# MCU_Main.net
KiCad netlist of a schematic drawn in Altium Designer
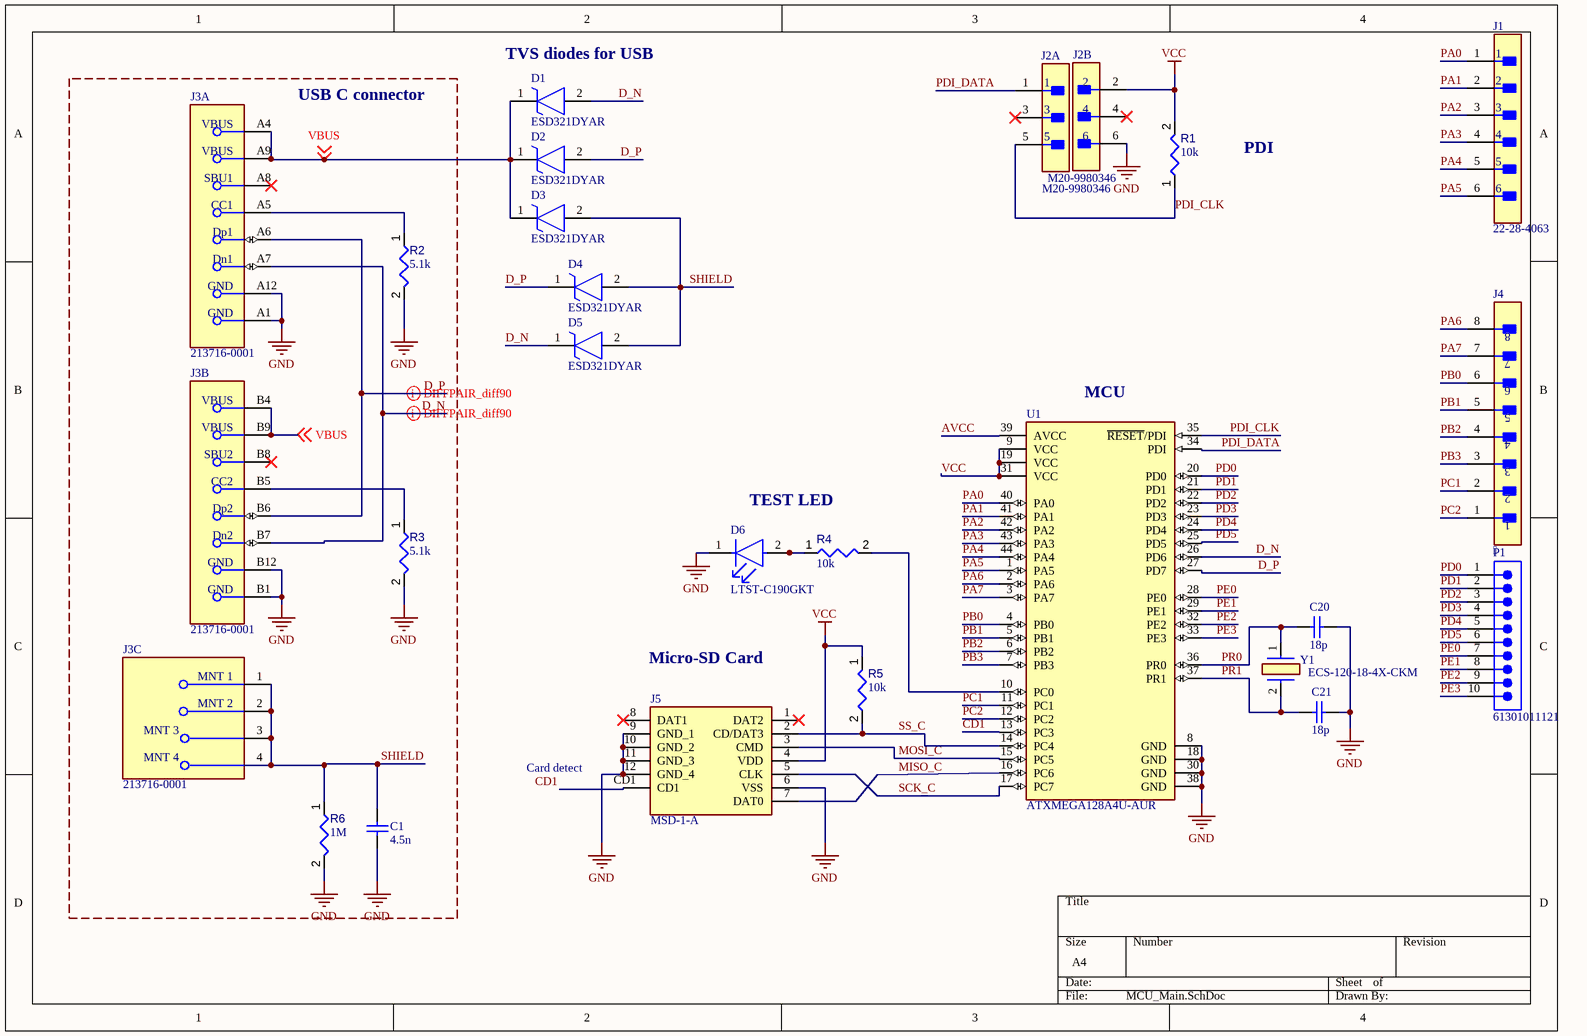
[diagram p0: MCU_Main.SchDoc]

(export (version "E")
  (design (tool "Eeschema 10.0.6"))
  (components
    (comp (ref "C1")
      (value "4.5n")
      (footprint "WCAP-CSGP_0402_L1W0.5H0.5")
      (description "CAP CER 10000PF 50V X7R 0402")
      (fields (field (name "TOLERANCE") "10%"))
      (libsource (lib "Altium Content Vault") (part "Capacitor_Non-Polarized"))
    )
    (comp (ref "C20")
      (value "18p")
      (footprint "WCAP-CSGP_0402_L1W0.5H0.5")
      (description "CAP CER 10000PF 50V X7R 0402")
      (fields (field (name "TOLERANCE") "10%"))
      (libsource (lib "Altium Content Vault") (part "Capacitor_Non-Polarized"))
    )
    (comp (ref "C21")
      (value "18p")
      (footprint "WCAP-CSGP_0402_L1W0.5H0.5")
      (description "CAP CER 10000PF 50V X7R 0402")
      (fields (field (name "TOLERANCE") "10%"))
      (libsource (lib "Altium Content Vault") (part "Capacitor_Non-Polarized"))
    )
    (comp (ref "D1")
      (value "ESD321DYAR")
      (footprint "SamacSys:SODFL1608X77N")
      (description "TVS Diode (Uni-directional)")
      (fields (field (name "MOUSER PART NUMBER") "595-ESD321DYAR"))
      (libsource (lib "*") (part "ESD321DYAR"))
    )
    (comp (ref "D2")
      (value "ESD321DYAR")
      (footprint "SamacSys:SODFL1608X77N")
      (description "TVS Diode (Uni-directional)")
      (fields (field (name "MOUSER PART NUMBER") "595-ESD321DYAR"))
      (libsource (lib "*") (part "ESD321DYAR"))
    )
    (comp (ref "D3")
      (value "ESD321DYAR")
      (footprint "SamacSys:SODFL1608X77N")
      (description "TVS Diode (Uni-directional)")
      (fields (field (name "MOUSER PART NUMBER") "595-ESD321DYAR"))
      (libsource (lib "*") (part "ESD321DYAR"))
    )
    (comp (ref "D4")
      (value "ESD321DYAR")
      (footprint "SamacSys:SODFL1608X77N")
      (description "TVS Diode (Uni-directional)")
      (fields (field (name "MOUSER PART NUMBER") "595-ESD321DYAR"))
      (libsource (lib "*") (part "ESD321DYAR"))
    )
    (comp (ref "D5")
      (value "ESD321DYAR")
      (footprint "SamacSys:SODFL1608X77N")
      (description "TVS Diode (Uni-directional)")
      (fields (field (name "MOUSER PART NUMBER") "595-ESD321DYAR"))
      (libsource (lib "*") (part "ESD321DYAR"))
    )
    (comp (ref "D6")
      (value "LTST-C190GKT")
      (footprint "FP-LTST-C190GKT-MFG")
      (description "LED GREEN CLEAR CHIP SMD")
      (fields (field (name "VOLTAGE") "2V"))
      (libsource (lib "Altium Content Vault") (part "8706943c75ba83719d021d2fdc84c58"))
    )
    (comp (ref "J1")
      (value "22-28-4063")
      (footprint "FP-22-28-4063-MFG")
      (description "CONN HEADER VERT 6POS 2.54MM")
      (libsource (lib "Altium Content Vault") (part "f2cb566baf1c37ab5a3b8e90bbeafd6"))
    )
    (comp (ref "J2")
      (value "M20-9980346")
      (footprint "FP-M20-9980346-MFG")
      (description "CONN HEADER VERT 6POS 2.54MM")
      (fields
        (field (name "MANUFACTURER") "Harwin")
        (field (name "OCTOPART") "https://octopart.com/m20-9980346-harwin-5436545")
      )
      (libsource (lib "Altium Content Vault") (part "2654a11fb13586ecb194516b1c997bc"))
    )
    (comp (ref "J3")
      (value "213716-0001")
      (footprint "FP-213716-0001-MFG")
      (description "CONN RCPT USB2.0 TYPE C 24POS RA")
      (libsource (lib "Altium Content Vault") (part "d371042584e5ad1ff312aac3cd0a0ad"))
    )
    (comp (ref "J4")
      (value "")
      (footprint "FP-M20-9990846-MFG")
      (description "CONN HEADER VERT 8POS 2.54MM")
      (libsource (lib "Altium Content Vault") (part "99ec2b232beb5d2356d4d77f6a047f0"))
    )
    (comp (ref "J5")
      (value "MSD-1-A")
      (footprint "SamacSys:MSD1A")
      (description "Connector")
      (fields (field (name "MOUSER PART NUMBER") "179-MSD-1-A"))
      (libsource (lib "*") (part "MSD-1-A"))
    )
    (comp (ref "P1")
      (value "61301011121")
      (footprint "61301011121")
      (libsource (lib "Altium Content Vault") (part "Header_Male_1R_10P"))
    )
    (comp (ref "R1")
      (value "10k")
      (footprint "RESC1005X40X25ML05T05")
      (description "Chip Resistor, 4.7 KOhm, +/- 1%, 63 mW, -55 to 155 degC, 0402 (1005 Metric)")
      (fields (field (name "TOLERANCE") "1%") (field (name "POWER") "63mW"))
      (libsource (lib "Christian Fenger") (part "RES-2"))
    )
    (comp (ref "R2")
      (value "5.1k")
      (footprint "RESC1005X40X25ML05T05")
      (description "Chip Resistor, 4.7 KOhm, +/- 1%, 63 mW, -55 to 155 degC, 0402 (1005 Metric)")
      (fields (field (name "TOLERANCE") "1%") (field (name "POWER") "63mW"))
      (libsource (lib "Christian Fenger") (part "RES-2"))
    )
    (comp (ref "R3")
      (value "5.1k")
      (footprint "RESC1005X40X25ML05T05")
      (description "Chip Resistor, 4.7 KOhm, +/- 1%, 63 mW, -55 to 155 degC, 0402 (1005 Metric)")
      (fields (field (name "TOLERANCE") "1%") (field (name "POWER") "63mW"))
      (libsource (lib "Christian Fenger") (part "RES-2"))
    )
    (comp (ref "R4")
      (value "10k")
      (footprint "RESC1005X40X25ML05T05")
      (description "Chip Resistor, 4.7 KOhm, +/- 1%, 63 mW, -55 to 155 degC, 0402 (1005 Metric)")
      (fields (field (name "TOLERANCE") "1%") (field (name "POWER") "63mW"))
      (libsource (lib "Christian Fenger") (part "RES-2"))
    )
    (comp (ref "R5")
      (value "10k")
      (footprint "RESC1005X40X25ML05T05")
      (description "Chip Resistor, 4.7 KOhm, +/- 1%, 63 mW, -55 to 155 degC, 0402 (1005 Metric)")
      (fields (field (name "TOLERANCE") "1%") (field (name "POWER") "63mW"))
      (libsource (lib "Christian Fenger") (part "RES-2"))
    )
    (comp (ref "R6")
      (value "1M")
      (footprint "RESC1005X40X25ML05T05")
      (description "Chip Resistor, 4.7 KOhm, +/- 1%, 63 mW, -55 to 155 degC, 0402 (1005 Metric)")
      (fields (field (name "TOLERANCE") "1%") (field (name "POWER") "63mW"))
      (libsource (lib "Christian Fenger") (part "RES-2"))
    )
    (comp (ref "U1")
      (value "ATXMEGA128A4U-AUR")
      (footprint "FP-C04-076-IPC_A")
      (description "IC MCU 8/16BIT 128KB FLSH 44TQFP")
      (libsource (lib "Altium Content Vault") (part "9626c523c69d53887b0765d3e361254"))
    )
    (comp (ref "Y1")
      (value "ECS-120-18-4X-CKM")
      (footprint "SamacSys:ECS120184XCKM")
      (description "Crystal or Oscillator")
      (fields (field (name "MOUSER PART NUMBER") "520-ECS120-18-4X-CKM"))
      (libsource (lib "*") (part "ECS-120-18-4X-CKM"))
    )
  )
  (nets
    (net (code "1") (name "/AVCC") (class "Default")
      (node (ref "U1") (pin "39") (pinfunction "AVCC_39") (pintype "power_in"))
    )
    (net (code "2") (name "/CD1") (class "Default")
      (node (ref "J5") (pin "CD1") (pinfunction "CD1_CD1") (pintype "passive"))
      (node (ref "U1") (pin "13") (pinfunction "PC3_13") (pintype "bidirectional"))
    )
    (net (code "3") (name "/D_N") (class "Default")
      (node (ref "D1") (pin "2") (pinfunction "A_2") (pintype "passive"))
      (node (ref "D5") (pin "1") (pinfunction "K_1") (pintype "passive"))
      (node (ref "J3") (pin "A7") (pinfunction "Dn1_A7") (pintype "bidirectional"))
      (node (ref "J3") (pin "B7") (pinfunction "Dn2_B7") (pintype "bidirectional"))
      (node (ref "U1") (pin "26") (pinfunction "PD6_26") (pintype "bidirectional"))
    )
    (net (code "4") (name "/D_P") (class "Default")
      (node (ref "D2") (pin "2") (pinfunction "A_2") (pintype "passive"))
      (node (ref "D4") (pin "1") (pinfunction "K_1") (pintype "passive"))
      (node (ref "J3") (pin "A6") (pinfunction "Dp1_A6") (pintype "bidirectional"))
      (node (ref "J3") (pin "B6") (pinfunction "Dp2_B6") (pintype "bidirectional"))
      (node (ref "U1") (pin "27") (pinfunction "PD7_27") (pintype "bidirectional"))
    )
    (net (code "6") (name "/MISO_C") (class "Default")
      (node (ref "J5") (pin "7") (pinfunction "DAT0_7") (pintype "passive"))
      (node (ref "U1") (pin "16") (pinfunction "PC6_16") (pintype "bidirectional"))
    )
    (net (code "7") (name "/MOSI_C") (class "Default")
      (node (ref "J5") (pin "3") (pinfunction "CMD_3") (pintype "passive"))
      (node (ref "U1") (pin "15") (pinfunction "PC5_15") (pintype "bidirectional"))
    )
    (net (code "8") (name "/PA0") (class "Default")
      (node (ref "J1") (pin "1") (pinfunction "1_1") (pintype "passive"))
      (node (ref "U1") (pin "40") (pinfunction "PA0_40") (pintype "bidirectional"))
    )
    (net (code "9") (name "/PA1") (class "Default")
      (node (ref "J1") (pin "2") (pinfunction "2_2") (pintype "passive"))
      (node (ref "U1") (pin "41") (pinfunction "PA1_41") (pintype "bidirectional"))
    )
    (net (code "10") (name "/PA2") (class "Default")
      (node (ref "J1") (pin "3") (pinfunction "3_3") (pintype "passive"))
      (node (ref "U1") (pin "42") (pinfunction "PA2_42") (pintype "bidirectional"))
    )
    (net (code "11") (name "/PA3") (class "Default")
      (node (ref "J1") (pin "4") (pinfunction "4_4") (pintype "passive"))
      (node (ref "U1") (pin "43") (pinfunction "PA3_43") (pintype "bidirectional"))
    )
    (net (code "12") (name "/PA4") (class "Default")
      (node (ref "J1") (pin "5") (pinfunction "5_5") (pintype "passive"))
      (node (ref "U1") (pin "44") (pinfunction "PA4_44") (pintype "bidirectional"))
    )
    (net (code "13") (name "/PA5") (class "Default")
      (node (ref "J1") (pin "6") (pinfunction "6_6") (pintype "passive"))
      (node (ref "U1") (pin "1") (pinfunction "PA5_1") (pintype "bidirectional"))
    )
    (net (code "14") (name "/PA6") (class "Default")
      (node (ref "J4") (pin "8") (pinfunction "8_8") (pintype "passive"))
      (node (ref "U1") (pin "2") (pinfunction "PA6_2") (pintype "bidirectional"))
    )
    (net (code "15") (name "/PA7") (class "Default")
      (node (ref "J4") (pin "7") (pinfunction "7_7") (pintype "passive"))
      (node (ref "U1") (pin "3") (pinfunction "PA7_3") (pintype "bidirectional"))
    )
    (net (code "16") (name "/PB0") (class "Default")
      (node (ref "J4") (pin "6") (pinfunction "6_6") (pintype "passive"))
      (node (ref "U1") (pin "4") (pinfunction "PB0_4") (pintype "bidirectional"))
    )
    (net (code "17") (name "/PB1") (class "Default")
      (node (ref "J4") (pin "5") (pinfunction "5_5") (pintype "passive"))
      (node (ref "U1") (pin "5") (pinfunction "PB1_5") (pintype "bidirectional"))
    )
    (net (code "18") (name "/PB2") (class "Default")
      (node (ref "J4") (pin "4") (pinfunction "4_4") (pintype "passive"))
      (node (ref "U1") (pin "6") (pinfunction "PB2_6") (pintype "bidirectional"))
    )
    (net (code "19") (name "/PB3") (class "Default")
      (node (ref "J4") (pin "3") (pinfunction "3_3") (pintype "passive"))
      (node (ref "U1") (pin "7") (pinfunction "PB3_7") (pintype "bidirectional"))
    )
    (net (code "20") (name "/PC1") (class "Default")
      (node (ref "J4") (pin "2") (pinfunction "2_2") (pintype "passive"))
      (node (ref "U1") (pin "11") (pinfunction "PC1_11") (pintype "bidirectional"))
    )
    (net (code "21") (name "/PC2") (class "Default")
      (node (ref "J4") (pin "1") (pinfunction "1_1") (pintype "passive"))
      (node (ref "U1") (pin "12") (pinfunction "PC2_12") (pintype "bidirectional"))
    )
    (net (code "22") (name "/PD0") (class "Default")
      (node (ref "P1") (pin "1") (pinfunction "1_1") (pintype "passive"))
      (node (ref "U1") (pin "20") (pinfunction "PD0_20") (pintype "bidirectional"))
    )
    (net (code "23") (name "/PD1") (class "Default")
      (node (ref "P1") (pin "2") (pinfunction "2_2") (pintype "passive"))
      (node (ref "U1") (pin "21") (pinfunction "PD1_21") (pintype "bidirectional"))
    )
    (net (code "24") (name "/PD2") (class "Default")
      (node (ref "P1") (pin "3") (pinfunction "3_3") (pintype "passive"))
      (node (ref "U1") (pin "22") (pinfunction "PD2_22") (pintype "bidirectional"))
    )
    (net (code "25") (name "/PD3") (class "Default")
      (node (ref "P1") (pin "4") (pinfunction "4_4") (pintype "passive"))
      (node (ref "U1") (pin "23") (pinfunction "PD3_23") (pintype "bidirectional"))
    )
    (net (code "26") (name "/PD4") (class "Default")
      (node (ref "P1") (pin "5") (pinfunction "5_5") (pintype "passive"))
      (node (ref "U1") (pin "24") (pinfunction "PD4_24") (pintype "bidirectional"))
    )
    (net (code "27") (name "/PD5") (class "Default")
      (node (ref "P1") (pin "6") (pinfunction "6_6") (pintype "passive"))
      (node (ref "U1") (pin "25") (pinfunction "PD5_25") (pintype "bidirectional"))
    )
    (net (code "28") (name "/PDI_CLK") (class "Default")
      (node (ref "J2") (pin "5") (pinfunction "5_5") (pintype "passive"))
      (node (ref "R1") (pin "1") (pinfunction "1_1") (pintype "passive"))
      (node (ref "U1") (pin "35") (pinfunction "~{RESET}/PDI_35") (pintype "input"))
    )
    (net (code "29") (name "/PDI_DATA") (class "Default")
      (node (ref "J2") (pin "1") (pinfunction "1_1") (pintype "passive"))
      (node (ref "U1") (pin "34") (pinfunction "PDI_34") (pintype "input"))
    )
    (net (code "30") (name "/PE0") (class "Default")
      (node (ref "P1") (pin "7") (pinfunction "7_7") (pintype "passive"))
      (node (ref "U1") (pin "28") (pinfunction "PE0_28") (pintype "bidirectional"))
    )
    (net (code "31") (name "/PE1") (class "Default")
      (node (ref "P1") (pin "8") (pinfunction "8_8") (pintype "passive"))
      (node (ref "U1") (pin "29") (pinfunction "PE1_29") (pintype "bidirectional"))
    )
    (net (code "32") (name "/PE2") (class "Default")
      (node (ref "P1") (pin "9") (pinfunction "9_9") (pintype "passive"))
      (node (ref "U1") (pin "32") (pinfunction "PE2_32") (pintype "bidirectional"))
    )
    (net (code "33") (name "/PE3") (class "Default")
      (node (ref "P1") (pin "10") (pinfunction "10_10") (pintype "passive"))
      (node (ref "U1") (pin "33") (pinfunction "PE3_33") (pintype "bidirectional"))
    )
    (net (code "34") (name "/PR0") (class "Default")
      (node (ref "C20") (pin "2") (pinfunction "2_2") (pintype "passive"))
      (node (ref "U1") (pin "36") (pinfunction "PR0_36") (pintype "bidirectional"))
      (node (ref "Y1") (pin "1") (pinfunction "CRYSTAL_1_1") (pintype "passive"))
    )
    (net (code "35") (name "/PR1") (class "Default")
      (node (ref "C21") (pin "2") (pinfunction "2_2") (pintype "passive"))
      (node (ref "U1") (pin "37") (pinfunction "PR1_37") (pintype "bidirectional"))
      (node (ref "Y1") (pin "2") (pinfunction "CRYSTAL_2_2") (pintype "passive"))
    )
    (net (code "36") (name "/SCK_C") (class "Default")
      (node (ref "J5") (pin "5") (pinfunction "CLK_5") (pintype "passive"))
      (node (ref "U1") (pin "17") (pinfunction "PC7_17") (pintype "bidirectional"))
    )
    (net (code "37") (name "/SHIELD") (class "Default")
      (node (ref "C1") (pin "2") (pinfunction "2_2") (pintype "passive"))
      (node (ref "D3") (pin "2") (pinfunction "A_2") (pintype "passive"))
      (node (ref "D4") (pin "2") (pinfunction "A_2") (pintype "passive"))
      (node (ref "D5") (pin "2") (pinfunction "A_2") (pintype "passive"))
      (node (ref "J3") (pin "1") (pinfunction "MNT_1_1") (pintype "passive"))
      (node (ref "J3") (pin "2") (pinfunction "MNT_2_2") (pintype "passive"))
      (node (ref "J3") (pin "3") (pinfunction "MNT_3_3") (pintype "passive"))
      (node (ref "J3") (pin "4") (pinfunction "MNT_4_4") (pintype "passive"))
      (node (ref "R6") (pin "1") (pinfunction "1_1") (pintype "passive"))
    )
    (net (code "38") (name "/SS_C") (class "Default")
      (node (ref "J5") (pin "2") (pinfunction "CD/DAT3_2") (pintype "passive"))
      (node (ref "R5") (pin "2") (pinfunction "2_2") (pintype "passive"))
      (node (ref "U1") (pin "14") (pinfunction "PC4_14") (pintype "bidirectional"))
    )
    (net (code "39") (name "GND") (class "Default")
      (node (ref "C1") (pin "1") (pinfunction "1_1") (pintype "passive"))
      (node (ref "C20") (pin "1") (pinfunction "1_1") (pintype "passive"))
      (node (ref "C21") (pin "1") (pinfunction "1_1") (pintype "passive"))
      (node (ref "D6") (pin "1") (pinfunction "C_1") (pintype "passive"))
      (node (ref "J2") (pin "6") (pinfunction "6_6") (pintype "passive"))
      (node (ref "J3") (pin "A1") (pinfunction "GND_A1") (pintype "power_in"))
      (node (ref "J3") (pin "A12") (pinfunction "GND_A12") (pintype "power_in"))
      (node (ref "J3") (pin "B1") (pinfunction "GND_B1") (pintype "power_in"))
      (node (ref "J3") (pin "B12") (pinfunction "GND_B12") (pintype "power_in"))
      (node (ref "J5") (pin "10") (pinfunction "GND_2_10") (pintype "passive"))
      (node (ref "J5") (pin "11") (pinfunction "GND_3_11") (pintype "passive"))
      (node (ref "J5") (pin "12") (pinfunction "GND_4_12") (pintype "passive"))
      (node (ref "J5") (pin "6") (pinfunction "VSS_6") (pintype "passive"))
      (node (ref "J5") (pin "9") (pinfunction "GND_1_9") (pintype "passive"))
      (node (ref "R2") (pin "2") (pinfunction "2_2") (pintype "passive"))
      (node (ref "R3") (pin "2") (pinfunction "2_2") (pintype "passive"))
      (node (ref "R6") (pin "2") (pinfunction "2_2") (pintype "passive"))
      (node (ref "U1") (pin "18") (pinfunction "GND_18") (pintype "power_in"))
      (node (ref "U1") (pin "30") (pinfunction "GND_30") (pintype "power_in"))
      (node (ref "U1") (pin "38") (pinfunction "GND_38") (pintype "power_in"))
      (node (ref "U1") (pin "8") (pinfunction "GND_8") (pintype "power_in"))
    )
    (net (code "40") (name "Net-(D6-A)") (class "Default")
      (node (ref "D6") (pin "2") (pinfunction "A_2") (pintype "passive"))
      (node (ref "R4") (pin "1") (pinfunction "1_1") (pintype "passive"))
    )
    (net (code "41") (name "Net-(J3A-CC1)") (class "Default")
      (node (ref "J3") (pin "A5") (pinfunction "CC1_A5") (pintype "passive"))
      (node (ref "R2") (pin "1") (pinfunction "1_1") (pintype "passive"))
    )
    (net (code "42") (name "Net-(J3B-CC2)") (class "Default")
      (node (ref "J3") (pin "B5") (pinfunction "CC2_B5") (pintype "passive"))
      (node (ref "R3") (pin "1") (pinfunction "1_1") (pintype "passive"))
    )
    (net (code "43") (name "Net-(U1-PC0)") (class "Default")
      (node (ref "R4") (pin "2") (pinfunction "2_2") (pintype "passive"))
      (node (ref "U1") (pin "10") (pinfunction "PC0_10") (pintype "bidirectional"))
    )
    (net (code "44") (name "VBUS") (class "Default")
      (node (ref "D1") (pin "1") (pinfunction "K_1") (pintype "passive"))
      (node (ref "D2") (pin "1") (pinfunction "K_1") (pintype "passive"))
      (node (ref "D3") (pin "1") (pinfunction "K_1") (pintype "passive"))
      (node (ref "J3") (pin "A4") (pinfunction "VBUS_A4") (pintype "power_in"))
      (node (ref "J3") (pin "A9") (pinfunction "VBUS_A9") (pintype "power_in"))
      (node (ref "J3") (pin "B4") (pinfunction "VBUS_B4") (pintype "power_in"))
      (node (ref "J3") (pin "B9") (pinfunction "VBUS_B9") (pintype "power_in"))
    )
    (net (code "45") (name "VCC") (class "Default")
      (node (ref "J2") (pin "2") (pinfunction "2_2") (pintype "passive"))
      (node (ref "J5") (pin "4") (pinfunction "VDD_4") (pintype "passive"))
      (node (ref "R1") (pin "2") (pinfunction "2_2") (pintype "passive"))
      (node (ref "R5") (pin "1") (pinfunction "1_1") (pintype "passive"))
      (node (ref "U1") (pin "19") (pinfunction "VCC_19") (pintype "power_in"))
      (node (ref "U1") (pin "31") (pinfunction "VCC_31") (pintype "power_in"))
      (node (ref "U1") (pin "9") (pinfunction "VCC_9") (pintype "power_in"))
    )
    (net (code "46") (name "unconnected-(J2-Pad3)") (class "Default")
      (node (ref "J2") (pin "3") (pinfunction "3_3") (pintype "passive+no_connect"))
    )
    (net (code "47") (name "unconnected-(J2-Pad4)") (class "Default")
      (node (ref "J2") (pin "4") (pinfunction "4_4") (pintype "passive+no_connect"))
    )
    (net (code "48") (name "unconnected-(J3A-SBU1-PadA8)") (class "Default")
      (node (ref "J3") (pin "A8") (pinfunction "SBU1_A8") (pintype "passive+no_connect"))
    )
    (net (code "49") (name "unconnected-(J3B-SBU2-PadB8)") (class "Default")
      (node (ref "J3") (pin "B8") (pinfunction "SBU2_B8") (pintype "passive+no_connect"))
    )
    (net (code "50") (name "unconnected-(J5-DAT1-Pad8)") (class "Default")
      (node (ref "J5") (pin "8") (pinfunction "DAT1_8") (pintype "passive+no_connect"))
    )
    (net (code "51") (name "unconnected-(J5-DAT2-Pad1)") (class "Default")
      (node (ref "J5") (pin "1") (pinfunction "DAT2_1") (pintype "passive+no_connect"))
    )
  )
)
